# Fuel-Gauge.net
KiCad netlist of a schematic drawn in Altium Designer
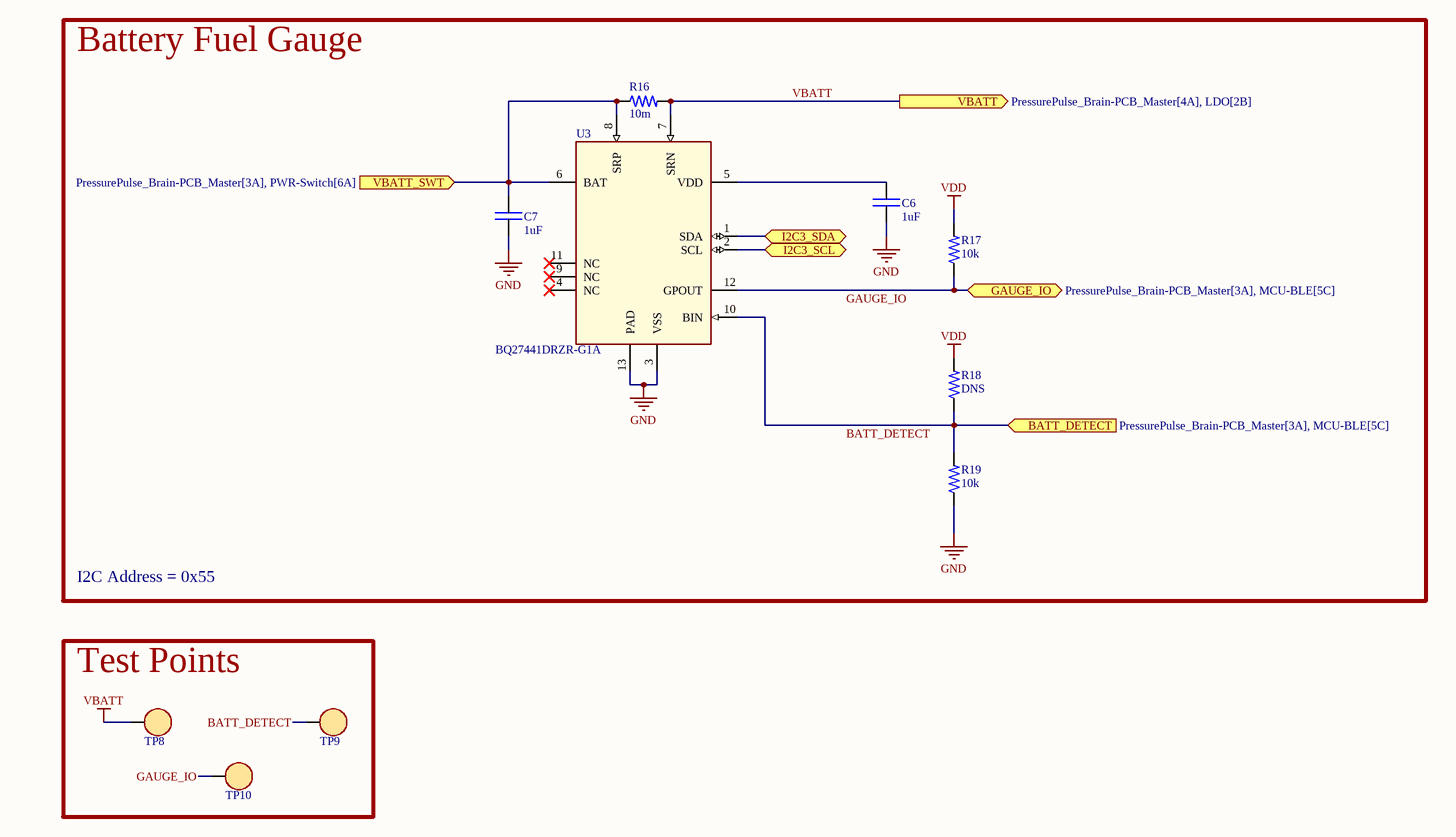
[diagram p0: Fuel-Gauge.SchDoc]

(export (version "E")
  (design (tool "Eeschema 10.0.6"))
  (components
    (comp (ref "C6")
      (value "1uF")
      (footprint "PressurePulse:0402C")
      (description "Capacitor")
      (fields (field (name "Comment") "CAP"))
      (libsource (lib "PressurePulse") (part "CAP"))
    )
    (comp (ref "C7")
      (value "1uF")
      (footprint "PressurePulse:0402C")
      (description "Capacitor")
      (fields (field (name "Comment") "CAP"))
      (libsource (lib "PressurePulse") (part "CAP"))
    )
    (comp (ref "R16")
      (value "10m")
      (footprint "PressurePulse:2512R")
      (description "3W 10m Ohm Current Sense Resistor")
      (fields (field (name "TOLERANCE") "1%") (field (name "Comment") "RES - CURRENT SENSE"))
      (libsource (lib "PressurePulse") (part "RES - CURRENT SENSE"))
    )
    (comp (ref "R17")
      (value "10k")
      (footprint "PressurePulse:0402R")
      (description "Resistor")
      (fields (field (name "Comment") "RES"))
      (libsource (lib "PressurePulse") (part "RES"))
    )
    (comp (ref "R18")
      (value "DNS")
      (footprint "PressurePulse:0402R")
      (description "Resistor")
      (fields (field (name "Comment") "RES"))
      (libsource (lib "PressurePulse") (part "RES"))
    )
    (comp (ref "R19")
      (value "10k")
      (footprint "PressurePulse:0402R")
      (description "Resistor")
      (fields (field (name "Comment") "RES"))
      (libsource (lib "PressurePulse") (part "RES"))
    )
    (comp (ref "TP8")
      (value "RH-5019")
      (footprint "PressurePulse:TP - RH-5019")
      (fields (field (name "MFR") "ronghe"))
      (libsource (lib "PressurePulse") (part "TEST POINT"))
    )
    (comp (ref "TP9")
      (value "RH-5019")
      (footprint "PressurePulse:TP - RH-5019")
      (fields (field (name "MFR") "ronghe"))
      (libsource (lib "PressurePulse") (part "TEST POINT"))
    )
    (comp (ref "TP10")
      (value "RH-5019")
      (footprint "PressurePulse:TP - RH-5019")
      (fields (field (name "MFR") "ronghe"))
      (libsource (lib "PressurePulse") (part "TEST POINT"))
    )
    (comp (ref "U3")
      (value "BQ27441DRZR-G1A")
      (footprint "PressurePulse:bq27441-G1")
      (description "No Description Available")
      (fields (field (name "MFR") "Texas Instruments"))
      (libsource (lib "PressurePulse") (part "BATT FUEL GAUGE"))
    )
  )
  (nets
    (net (code "1") (name "/BATT_DETECT") (class "Default")
      (node (ref "R18") (pin "1") (pinfunction "1_1") (pintype "passive"))
      (node (ref "R19") (pin "2") (pinfunction "2_2") (pintype "passive"))
      (node (ref "TP9") (pin "1") (pinfunction "1_1") (pintype "passive"))
      (node (ref "U3") (pin "10") (pinfunction "BIN_10") (pintype "input"))
    )
    (net (code "2") (name "/GAUGE_IO") (class "Default")
      (node (ref "R17") (pin "1") (pinfunction "1_1") (pintype "passive"))
      (node (ref "TP10") (pin "1") (pinfunction "1_1") (pintype "passive"))
      (node (ref "U3") (pin "12") (pinfunction "GPOUT_12") (pintype "open_collector"))
    )
    (net (code "3") (name "/I2C3_SCL") (class "Default")
      (node (ref "U3") (pin "2") (pinfunction "SCL_2") (pintype "bidirectional"))
    )
    (net (code "4") (name "/I2C3_SDA") (class "Default")
      (node (ref "U3") (pin "1") (pinfunction "SDA_1") (pintype "bidirectional"))
    )
    (net (code "5") (name "/VBATT_SWT") (class "Default")
      (node (ref "C7") (pin "2") (pinfunction "2_2") (pintype "passive"))
      (node (ref "R16") (pin "1") (pinfunction "1_1") (pintype "passive"))
      (node (ref "U3") (pin "6") (pinfunction "BAT_6") (pintype "power_in"))
      (node (ref "U3") (pin "8") (pinfunction "SRP_8") (pintype "input"))
    )
    (net (code "6") (name "GND") (class "Default")
      (node (ref "C6") (pin "1") (pinfunction "1_1") (pintype "passive"))
      (node (ref "C7") (pin "1") (pinfunction "1_1") (pintype "passive"))
      (node (ref "R19") (pin "1") (pinfunction "1_1") (pintype "passive"))
      (node (ref "U3") (pin "13") (pinfunction "PAD_13") (pintype "power_in"))
      (node (ref "U3") (pin "3") (pinfunction "VSS_3") (pintype "power_in"))
    )
    (net (code "7") (name "Net-(U3-VDD)") (class "Default")
      (node (ref "C6") (pin "2") (pinfunction "2_2") (pintype "passive"))
      (node (ref "U3") (pin "5") (pinfunction "VDD_5") (pintype "power_in"))
    )
    (net (code "8") (name "VBATT") (class "Default")
      (node (ref "R16") (pin "2") (pinfunction "2_2") (pintype "passive"))
      (node (ref "TP8") (pin "1") (pinfunction "1_1") (pintype "passive"))
      (node (ref "U3") (pin "7") (pinfunction "SRN_7") (pintype "input"))
    )
    (net (code "9") (name "VDD") (class "Default")
      (node (ref "R17") (pin "2") (pinfunction "2_2") (pintype "passive"))
      (node (ref "R18") (pin "2") (pinfunction "2_2") (pintype "passive"))
    )
    (net (code "10") (name "unconnected-(U3-NC-Pad4)") (class "Default")
      (node (ref "U3") (pin "4") (pinfunction "NC_4") (pintype "passive+no_connect"))
    )
    (net (code "11") (name "unconnected-(U3-NC-Pad9)") (class "Default")
      (node (ref "U3") (pin "9") (pinfunction "NC_9") (pintype "passive+no_connect"))
    )
    (net (code "12") (name "unconnected-(U3-NC-Pad11)") (class "Default")
      (node (ref "U3") (pin "11") (pinfunction "NC_11") (pintype "passive+no_connect"))
    )
  )
)
